# lm4550.net
KiCad netlist of a schematic drawn in Altium Designer
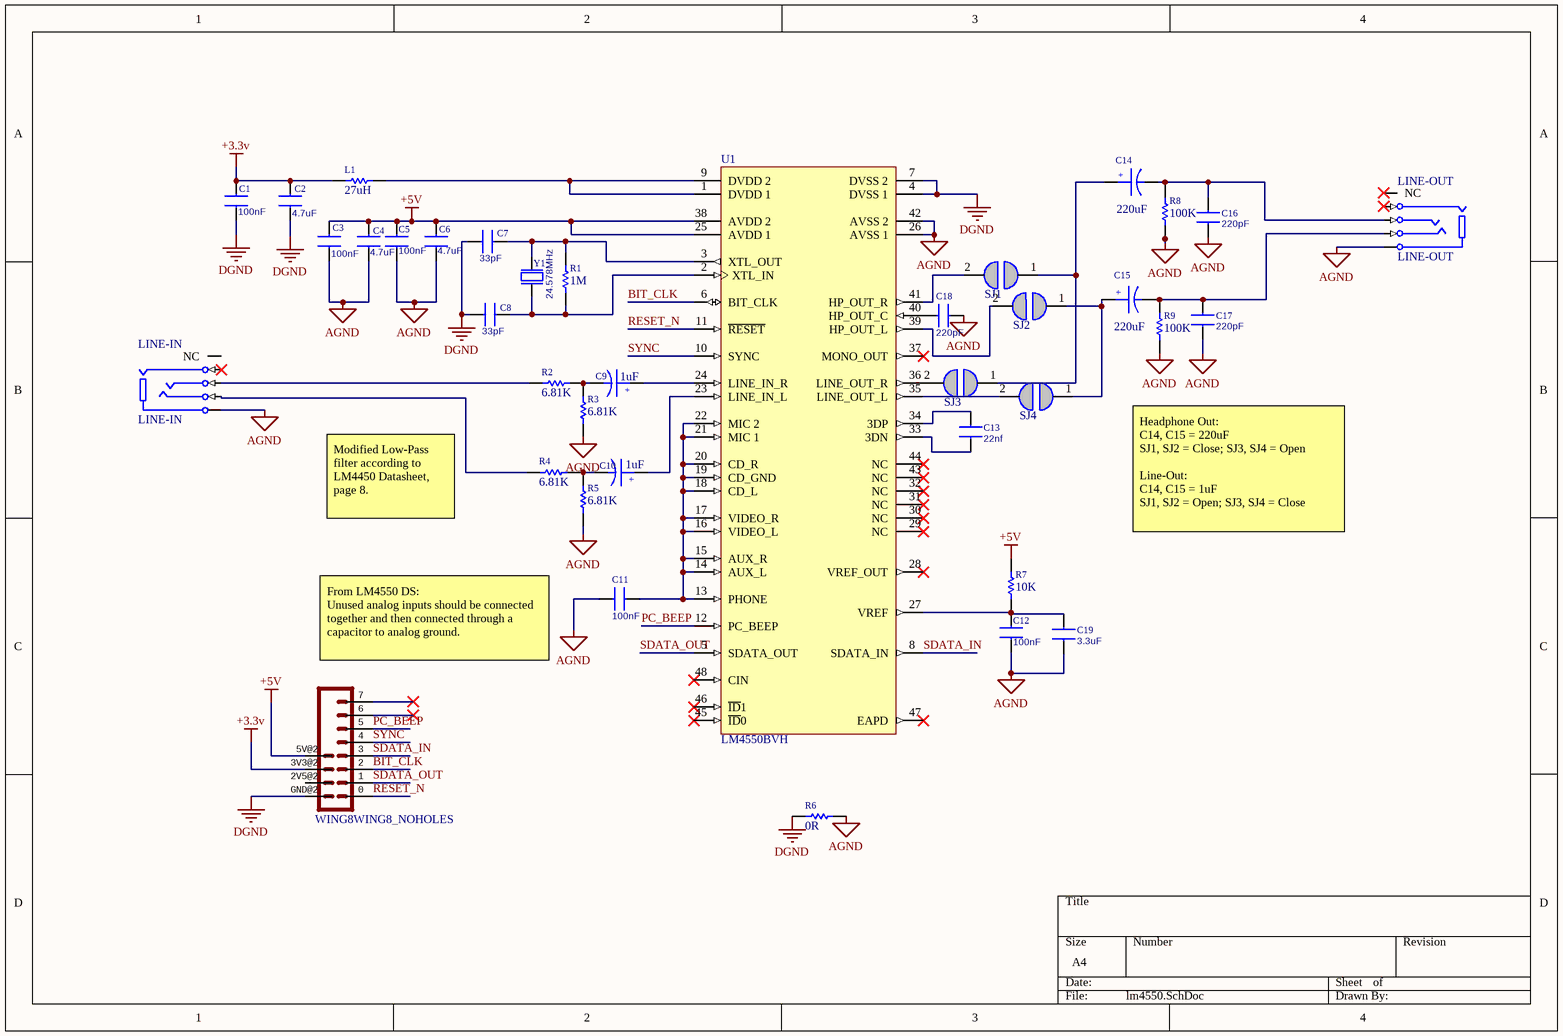
[diagram p0: lm4550.SchDoc]

(export (version "E")
  (design (tool "Eeschema 10.0.6"))
  (components
    (comp (ref "C1")
      (value "100nF")
      (footprint "MH - RCLDSX:C0603")
      (description "Ceramic Capactor size 0603")
      (libsource (lib "MH - RCLDSX") (part "C0603"))
    )
    (comp (ref "C2")
      (value "4.7uF")
      (footprint "C0805")
      (description "Ceramic Capactor size 0805")
      (libsource (lib "MH - RCLDSX") (part "C0805"))
    )
    (comp (ref "C3")
      (value "100nF")
      (footprint "C0603")
      (description "Ceramic Capactor size 0603")
      (libsource (lib "MH - RCLDSX") (part "C0603"))
    )
    (comp (ref "C4")
      (value "4.7uF")
      (footprint "C0805")
      (description "Ceramic Capactor size 0805")
      (libsource (lib "MH - RCLDSX") (part "C0805"))
    )
    (comp (ref "C5")
      (value "100nF")
      (footprint "C0603")
      (description "Ceramic Capactor size 0603")
      (libsource (lib "MH - RCLDSX") (part "C0603"))
    )
    (comp (ref "C6")
      (value "4.7uF")
      (footprint "C0805")
      (description "Ceramic Capactor size 0805")
      (libsource (lib "MH - RCLDSX") (part "C0805"))
    )
    (comp (ref "C7")
      (value "33pF")
      (footprint "C0603")
      (description "Ceramic Capactor size 0603")
      (libsource (lib "MH - RCLDSX") (part "C0603"))
    )
    (comp (ref "C8")
      (value "33pF")
      (footprint "C0603")
      (description "Ceramic Capactor size 0603")
      (libsource (lib "MH - RCLDSX") (part "C0603"))
    )
    (comp (ref "C9")
      (value "1uF")
      (footprint "CPM3216")
      (description "Tantalium Capacitor size A (3216 Metric)")
      (libsource (lib "MH - RCLDSX") (part "CPM3216"))
    )
    (comp (ref "C10")
      (value "1uF")
      (footprint "CPM3216")
      (description "Tantalium Capacitor size A (3216 Metric)")
      (libsource (lib "MH - RCLDSX") (part "CPM3216"))
    )
    (comp (ref "C11")
      (value "100nF")
      (footprint "C0603")
      (description "Ceramic Capactor size 0603")
      (libsource (lib "MH - RCLDSX") (part "C0603"))
    )
    (comp (ref "C12")
      (value "100nF")
      (footprint "C0603")
      (description "Ceramic Capactor size 0603")
      (libsource (lib "MH - RCLDSX") (part "C0603"))
    )
    (comp (ref "C13")
      (value "22nf")
      (footprint "C0603")
      (description "Ceramic Capactor size 0603")
      (libsource (lib "MH - RCLDSX") (part "C0603"))
    )
    (comp (ref "C14")
      (value "220uF")
      (footprint "CPM7343")
      (description "Tantalium Capacitor size D (7343 Metric)")
      (libsource (lib "MH - RCLDSX") (part "CPM7343"))
    )
    (comp (ref "C15")
      (value "220uF")
      (footprint "CPM7343")
      (description "Tantalium Capacitor size D (7343 Metric)")
      (libsource (lib "MH - RCLDSX") (part "CPM7343"))
    )
    (comp (ref "C16")
      (value "220pF")
      (footprint "C0805")
      (description "Ceramic Capactor size 0805")
      (libsource (lib "MH - RCLDSX") (part "C0805"))
    )
    (comp (ref "C17")
      (value "220pF")
      (footprint "C0805")
      (description "Ceramic Capactor size 0805")
      (libsource (lib "MH - RCLDSX") (part "C0805"))
    )
    (comp (ref "C18")
      (value "220pF")
      (footprint "C0805")
      (description "Ceramic Capactor size 0805")
      (libsource (lib "MH - RCLDSX") (part "C0805"))
    )
    (comp (ref "C19")
      (value "3.3uF")
      (footprint "C0805")
      (description "Ceramic Capactor size 0805")
      (libsource (lib "MH - RCLDSX") (part "C0805"))
    )
    (comp (ref "L1")
      (value "27uH")
      (footprint "R0805")
      (description "SMD Chip Inductor size 0805")
      (libsource (lib "MH - RCLDSX") (part "R0805"))
    )
    (comp (ref "LINE-IN")
      (value "LINE-IN")
      (footprint "PJ-386D")
      (description "Phone Jack, PJ-386D Series, Right Angle, SM, 4-Conductor Open Circuit")
      (fields (field (name "PUBLISHER") "Altium Limited"))
      (libsource (lib "Contact Technology Phone Jack") (part "TSH-3864D"))
    )
    (comp (ref "LINE-OUT")
      (value "LINE-OUT")
      (footprint "PJ-386D")
      (description "Phone Jack, PJ-386D Series, Right Angle, SM, 4-Conductor Open Circuit")
      (fields (field (name "PUBLISHER") "Altium Limited"))
      (libsource (lib "Contact Technology Phone Jack") (part "TSH-3864D"))
    )
    (comp (ref "P1")
      (value "WING8WING8_NOHOLES")
      (footprint "WINGSIDE_8BIT_NOHOLES")
      (libsource (lib "Papilio") (part "WING8WING8_NOHOLES"))
    )
    (comp (ref "R1")
      (value "1M")
      (footprint "R0805")
      (description "Chip Resistor size 0805")
      (libsource (lib "MH - RCLDSX") (part "R0805"))
    )
    (comp (ref "R2")
      (value "6.81K")
      (footprint "R0805")
      (description "Chip Resistor size 0805")
      (libsource (lib "MH - RCLDSX") (part "R0805"))
    )
    (comp (ref "R3")
      (value "6.81K")
      (footprint "R0805")
      (description "Chip Resistor size 0805")
      (libsource (lib "MH - RCLDSX") (part "R0805"))
    )
    (comp (ref "R4")
      (value "6.81K")
      (footprint "R0805")
      (description "Chip Resistor size 0805")
      (libsource (lib "MH - RCLDSX") (part "R0805"))
    )
    (comp (ref "R5")
      (value "6.81K")
      (footprint "R0805")
      (description "Chip Resistor size 0805")
      (libsource (lib "MH - RCLDSX") (part "R0805"))
    )
    (comp (ref "R6")
      (value "0R")
      (footprint "R0805")
      (description "Chip Resistor size 0805")
      (libsource (lib "MH - RCLDSX") (part "R0805"))
    )
    (comp (ref "R7")
      (value "10K")
      (footprint "R0805")
      (description "Chip Resistor size 0805")
      (libsource (lib "MH - RCLDSX") (part "R0805"))
    )
    (comp (ref "R8")
      (value "100K")
      (footprint "R0805")
      (description "Chip Resistor size 0805")
      (libsource (lib "MH - RCLDSX") (part "R0805"))
    )
    (comp (ref "R9")
      (value "100K")
      (footprint "R0805")
      (description "Chip Resistor size 0805")
      (libsource (lib "MH - RCLDSX") (part "R0805"))
    )
    (comp (ref "SJ1")
      (value "Solder Junction")
      (footprint "Solde Junction")
      (libsource (lib "MH - Connectors") (part "Solder Junction"))
    )
    (comp (ref "SJ2")
      (value "Solder Junction")
      (footprint "Solde Junction")
      (libsource (lib "MH - Connectors") (part "Solder Junction"))
    )
    (comp (ref "SJ3")
      (value "Solder Junction")
      (footprint "Solde Junction")
      (libsource (lib "MH - Connectors") (part "Solder Junction"))
    )
    (comp (ref "SJ4")
      (value "Solder Junction")
      (footprint "Solde Junction")
      (libsource (lib "MH - Connectors") (part "Solder Junction"))
    )
    (comp (ref "U1")
      (value "LM4550BVH")
      (footprint "VBH48A_N")
      (description "AC '97 Rev 2.1 Codec with Sample Rate Conversion and National 3D Sound, 48-pin LQFP")
      (fields
        (field (name "MANUFACTURER") "National Semiconductor")
        (field (name "PUBLISHER") "Altium Limited")
      )
      (libsource (lib "NSC OtherParts") (part "LM4550BVH"))
    )
    (comp (ref "Y1")
      (value "24.578MHz")
      (footprint "HC-49-S3")
      (description "XTAL Trough Hole")
      (libsource (lib "MH - RCLDSX") (part "XTAL_TH"))
    )
  )
  (nets
    (net (code "1") (name "+3.3v") (class "Default")
      (node (ref "C1") (pin "2") (pintype "passive"))
      (node (ref "C2") (pin "2") (pintype "passive"))
      (node (ref "L1") (pin "2") (pinfunction "2_2") (pintype "passive"))
      (node (ref "P1") (pin "3V3@2") (pinfunction "3V3_3V3@2") (pintype "passive"))
    )
    (net (code "2") (name "+5V") (class "Default")
      (node (ref "C3") (pin "2") (pintype "passive"))
      (node (ref "C4") (pin "2") (pintype "passive"))
      (node (ref "C5") (pin "2") (pintype "passive"))
      (node (ref "C6") (pin "2") (pintype "passive"))
      (node (ref "P1") (pin "5V@2") (pinfunction "5V_5V@2") (pintype "passive"))
      (node (ref "R7") (pin "2") (pinfunction "2_2") (pintype "passive"))
      (node (ref "U1") (pin "25") (pinfunction "AVDD_1_25") (pintype "power_in"))
      (node (ref "U1") (pin "38") (pinfunction "AVDD_2_38") (pintype "power_in"))
    )
    (net (code "3") (name "/BIT_CLK") (class "Default")
      (node (ref "P1") (pin "2") (pinfunction "3_2") (pintype "passive"))
      (node (ref "U1") (pin "6") (pinfunction "BIT_CLK_6") (pintype "bidirectional"))
    )
    (net (code "4") (name "/PC_BEEP") (class "Default")
      (node (ref "P1") (pin "5") (pinfunction "6_5") (pintype "passive"))
      (node (ref "U1") (pin "12") (pinfunction "PC_BEEP_12") (pintype "input"))
    )
    (net (code "5") (name "/RESET_N") (class "Default")
      (node (ref "P1") (pin "0") (pinfunction "1_0") (pintype "passive"))
      (node (ref "U1") (pin "11") (pinfunction "~{RESET}_11") (pintype "input"))
    )
    (net (code "6") (name "/SDATA_IN") (class "Default")
      (node (ref "P1") (pin "3") (pinfunction "4_3") (pintype "passive"))
      (node (ref "U1") (pin "8") (pinfunction "SDATA_IN_8") (pintype "output"))
    )
    (net (code "7") (name "/SDATA_OUT") (class "Default")
      (node (ref "P1") (pin "1") (pinfunction "2_1") (pintype "passive"))
      (node (ref "U1") (pin "5") (pinfunction "SDATA_OUT_5") (pintype "input"))
    )
    (net (code "8") (name "/SYNC") (class "Default")
      (node (ref "P1") (pin "4") (pinfunction "5_4") (pintype "passive"))
      (node (ref "U1") (pin "10") (pinfunction "SYNC_10") (pintype "input"))
    )
    (net (code "9") (name "AGND") (class "Default")
      (node (ref "C11") (pin "2") (pintype "passive"))
      (node (ref "C12") (pin "1") (pintype "passive"))
      (node (ref "C16") (pin "1") (pintype "passive"))
      (node (ref "C17") (pin "1") (pintype "passive"))
      (node (ref "C18") (pin "1") (pintype "passive"))
      (node (ref "C19") (pin "1") (pintype "passive"))
      (node (ref "C3") (pin "1") (pintype "passive"))
      (node (ref "C4") (pin "1") (pintype "passive"))
      (node (ref "C5") (pin "1") (pintype "passive"))
      (node (ref "C6") (pin "1") (pintype "passive"))
      (node (ref "LINE-IN") (pin "1") (pinfunction "S_1") (pintype "power_in"))
      (node (ref "LINE-OUT") (pin "1") (pinfunction "S_1") (pintype "power_in"))
      (node (ref "R3") (pin "1") (pinfunction "1_1") (pintype "passive"))
      (node (ref "R5") (pin "1") (pinfunction "1_1") (pintype "passive"))
      (node (ref "R6") (pin "2") (pinfunction "2_2") (pintype "passive"))
      (node (ref "R8") (pin "1") (pinfunction "1_1") (pintype "passive"))
      (node (ref "R9") (pin "1") (pinfunction "1_1") (pintype "passive"))
      (node (ref "U1") (pin "26") (pinfunction "AVSS_1_26") (pintype "power_in"))
      (node (ref "U1") (pin "42") (pinfunction "AVSS_2_42") (pintype "power_in"))
    )
    (net (code "10") (name "DGND") (class "Default")
      (node (ref "C1") (pin "1") (pintype "passive"))
      (node (ref "C2") (pin "1") (pintype "passive"))
      (node (ref "C7") (pin "2") (pintype "passive"))
      (node (ref "C8") (pin "2") (pintype "passive"))
      (node (ref "P1") (pin "GND@2") (pinfunction "GND_GND@2") (pintype "passive"))
      (node (ref "R6") (pin "1") (pinfunction "1_1") (pintype "passive"))
      (node (ref "U1") (pin "4") (pinfunction "DVSS_1_4") (pintype "power_in"))
      (node (ref "U1") (pin "7") (pinfunction "DVSS_2_7") (pintype "power_in"))
    )
    (net (code "11") (name "Net-(C9-Pad2)") (class "Default")
      (node (ref "C9") (pin "2") (pinfunction "2_2") (pintype "passive"))
      (node (ref "R2") (pin "2") (pinfunction "2_2") (pintype "passive"))
      (node (ref "R3") (pin "2") (pinfunction "2_2") (pintype "passive"))
    )
    (net (code "12") (name "Net-(C10-Pad2)") (class "Default")
      (node (ref "C10") (pin "2") (pinfunction "2_2") (pintype "passive"))
      (node (ref "R4") (pin "2") (pinfunction "2_2") (pintype "passive"))
      (node (ref "R5") (pin "2") (pinfunction "2_2") (pintype "passive"))
    )
    (net (code "13") (name "Net-(C14-Pad1)") (class "Default")
      (node (ref "C14") (pin "1") (pinfunction "1_1") (pintype "passive"))
      (node (ref "SJ1") (pin "1") (pinfunction "1_1") (pintype "passive"))
      (node (ref "SJ3") (pin "1") (pinfunction "1_1") (pintype "passive"))
    )
    (net (code "14") (name "Net-(C15-Pad1)") (class "Default")
      (node (ref "C15") (pin "1") (pinfunction "1_1") (pintype "passive"))
      (node (ref "SJ2") (pin "1") (pinfunction "1_1") (pintype "passive"))
      (node (ref "SJ4") (pin "1") (pinfunction "1_1") (pintype "passive"))
    )
    (net (code "15") (name "Net-(LINE-IN-R)") (class "Default")
      (node (ref "LINE-IN") (pin "3") (pinfunction "R_3") (pintype "input"))
      (node (ref "R4") (pin "1") (pinfunction "1_1") (pintype "passive"))
    )
    (net (code "16") (name "Net-(LINE-IN-T)") (class "Default")
      (node (ref "LINE-IN") (pin "2") (pinfunction "T_2") (pintype "input"))
      (node (ref "R2") (pin "1") (pinfunction "1_1") (pintype "passive"))
    )
    (net (code "17") (name "Net-(LINE-OUT-R)") (class "Default")
      (node (ref "C15") (pin "2") (pinfunction "2_2") (pintype "passive"))
      (node (ref "C17") (pin "2") (pintype "passive"))
      (node (ref "LINE-OUT") (pin "3") (pinfunction "R_3") (pintype "input"))
      (node (ref "R9") (pin "2") (pinfunction "2_2") (pintype "passive"))
    )
    (net (code "18") (name "Net-(LINE-OUT-T)") (class "Default")
      (node (ref "C14") (pin "2") (pinfunction "2_2") (pintype "passive"))
      (node (ref "C16") (pin "2") (pintype "passive"))
      (node (ref "LINE-OUT") (pin "2") (pinfunction "T_2") (pintype "input"))
      (node (ref "R8") (pin "2") (pinfunction "2_2") (pintype "passive"))
    )
    (net (code "19") (name "Net-(U1-3DN)") (class "Default")
      (node (ref "C13") (pin "2") (pintype "passive"))
      (node (ref "U1") (pin "33") (pinfunction "3DN_33") (pintype "output"))
    )
    (net (code "20") (name "Net-(U1-3DP)") (class "Default")
      (node (ref "C13") (pin "1") (pintype "passive"))
      (node (ref "U1") (pin "34") (pinfunction "3DP_34") (pintype "output"))
    )
    (net (code "21") (name "Net-(U1-AUX_L)") (class "Default")
      (node (ref "C11") (pin "1") (pintype "passive"))
      (node (ref "U1") (pin "13") (pinfunction "PHONE_13") (pintype "input"))
      (node (ref "U1") (pin "14") (pinfunction "AUX_L_14") (pintype "input"))
      (node (ref "U1") (pin "15") (pinfunction "AUX_R_15") (pintype "input"))
      (node (ref "U1") (pin "16") (pinfunction "VIDEO_L_16") (pintype "input"))
      (node (ref "U1") (pin "17") (pinfunction "VIDEO_R_17") (pintype "input"))
      (node (ref "U1") (pin "18") (pinfunction "CD_L_18") (pintype "input"))
      (node (ref "U1") (pin "19") (pinfunction "CD_GND_19") (pintype "input"))
      (node (ref "U1") (pin "20") (pinfunction "CD_R_20") (pintype "input"))
      (node (ref "U1") (pin "21") (pinfunction "MIC_1_21") (pintype "input"))
      (node (ref "U1") (pin "22") (pinfunction "MIC_2_22") (pintype "input"))
    )
    (net (code "22") (name "Net-(U1-DVDD_1)") (class "Default")
      (node (ref "L1") (pin "1") (pinfunction "1_1") (pintype "passive"))
      (node (ref "U1") (pin "1") (pinfunction "DVDD_1_1") (pintype "power_in"))
      (node (ref "U1") (pin "9") (pinfunction "DVDD_2_9") (pintype "power_in"))
    )
    (net (code "23") (name "Net-(U1-HP_OUT_C)") (class "Default")
      (node (ref "C18") (pin "2") (pintype "passive"))
      (node (ref "U1") (pin "40") (pinfunction "HP_OUT_C_40") (pintype "input"))
    )
    (net (code "24") (name "Net-(U1-HP_OUT_L)") (class "Default")
      (node (ref "SJ2") (pin "2") (pinfunction "2_2") (pintype "passive"))
      (node (ref "U1") (pin "39") (pinfunction "HP_OUT_L_39") (pintype "output"))
    )
    (net (code "25") (name "Net-(U1-HP_OUT_R)") (class "Default")
      (node (ref "SJ1") (pin "2") (pinfunction "2_2") (pintype "passive"))
      (node (ref "U1") (pin "41") (pinfunction "HP_OUT_R_41") (pintype "output"))
    )
    (net (code "26") (name "Net-(U1-LINE_IN_L)") (class "Default")
      (node (ref "C10") (pin "1") (pinfunction "1_1") (pintype "passive"))
      (node (ref "U1") (pin "23") (pinfunction "LINE_IN_L_23") (pintype "input"))
    )
    (net (code "27") (name "Net-(U1-LINE_IN_R)") (class "Default")
      (node (ref "C9") (pin "1") (pinfunction "1_1") (pintype "passive"))
      (node (ref "U1") (pin "24") (pinfunction "LINE_IN_R_24") (pintype "input"))
    )
    (net (code "28") (name "Net-(U1-LINE_OUT_L)") (class "Default")
      (node (ref "SJ4") (pin "2") (pinfunction "2_2") (pintype "passive"))
      (node (ref "U1") (pin "35") (pinfunction "LINE_OUT_L_35") (pintype "output"))
    )
    (net (code "29") (name "Net-(U1-LINE_OUT_R)") (class "Default")
      (node (ref "SJ3") (pin "2") (pinfunction "2_2") (pintype "passive"))
      (node (ref "U1") (pin "36") (pinfunction "LINE_OUT_R_36") (pintype "output"))
    )
    (net (code "30") (name "Net-(U1-VREF)") (class "Default")
      (node (ref "C12") (pin "2") (pintype "passive"))
      (node (ref "C19") (pin "2") (pintype "passive"))
      (node (ref "R7") (pin "1") (pinfunction "1_1") (pintype "passive"))
      (node (ref "U1") (pin "27") (pinfunction "VREF_27") (pintype "output"))
    )
    (net (code "31") (name "Net-(U1-XTL_IN)") (class "Default")
      (node (ref "C8") (pin "1") (pintype "passive"))
      (node (ref "R1") (pin "1") (pinfunction "1_1") (pintype "passive"))
      (node (ref "U1") (pin "2") (pinfunction "XTL_IN_2") (pintype "input"))
      (node (ref "Y1") (pin "2") (pintype "passive"))
    )
    (net (code "32") (name "Net-(U1-XTL_OUT)") (class "Default")
      (node (ref "C7") (pin "1") (pintype "passive"))
      (node (ref "R1") (pin "2") (pinfunction "2_2") (pintype "passive"))
      (node (ref "U1") (pin "3") (pinfunction "XTL_OUT_3") (pintype "output"))
      (node (ref "Y1") (pin "1") (pintype "passive"))
    )
    (net (code "33") (name "unconnected-(LINE-IN-NC-Pad10)") (class "Default")
      (node (ref "LINE-IN") (pin "10") (pinfunction "NC_10") (pintype "passive"))
    )
    (net (code "34") (name "unconnected-(LINE-IN-SN-Pad4)") (class "Default")
      (node (ref "LINE-IN") (pin "4") (pinfunction "SN_4") (pintype "input+no_connect"))
    )
    (net (code "35") (name "unconnected-(LINE-OUT-NC-Pad10)") (class "Default")
      (node (ref "LINE-OUT") (pin "10") (pinfunction "NC_10") (pintype "passive+no_connect"))
    )
    (net (code "36") (name "unconnected-(LINE-OUT-SN-Pad4)") (class "Default")
      (node (ref "LINE-OUT") (pin "4") (pinfunction "SN_4") (pintype "input+no_connect"))
    )
    (net (code "37") (name "unconnected-(P1-2V5-Pad2V5@2)") (class "Default")
      (node (ref "P1") (pin "2V5@2") (pinfunction "2V5_2V5@2") (pintype "passive"))
    )
    (net (code "38") (name "unconnected-(P1-7-Pad6)") (class "Default")
      (node (ref "P1") (pin "6") (pinfunction "7_6") (pintype "passive+no_connect"))
    )
    (net (code "39") (name "unconnected-(P1-8-Pad7)") (class "Default")
      (node (ref "P1") (pin "7") (pinfunction "8_7") (pintype "passive+no_connect"))
    )
    (net (code "40") (name "unconnected-(U1-CIN-Pad48)") (class "Default")
      (node (ref "U1") (pin "48") (pinfunction "CIN_48") (pintype "input+no_connect"))
    )
    (net (code "41") (name "unconnected-(U1-EAPD-Pad47)") (class "Default")
      (node (ref "U1") (pin "47") (pinfunction "EAPD_47") (pintype "output+no_connect"))
    )
    (net (code "42") (name "unconnected-(U1-MONO_OUT-Pad37)") (class "Default")
      (node (ref "U1") (pin "37") (pinfunction "MONO_OUT_37") (pintype "output+no_connect"))
    )
    (net (code "43") (name "unconnected-(U1-NC-Pad29)") (class "Default")
      (node (ref "U1") (pin "29") (pinfunction "NC_29") (pintype "passive+no_connect"))
    )
    (net (code "44") (name "unconnected-(U1-NC-Pad30)") (class "Default")
      (node (ref "U1") (pin "30") (pinfunction "NC_30") (pintype "passive+no_connect"))
    )
    (net (code "45") (name "unconnected-(U1-NC-Pad31)") (class "Default")
      (node (ref "U1") (pin "31") (pinfunction "NC_31") (pintype "passive+no_connect"))
    )
    (net (code "46") (name "unconnected-(U1-NC-Pad32)") (class "Default")
      (node (ref "U1") (pin "32") (pinfunction "NC_32") (pintype "passive+no_connect"))
    )
    (net (code "47") (name "unconnected-(U1-NC-Pad43)") (class "Default")
      (node (ref "U1") (pin "43") (pinfunction "NC_43") (pintype "passive+no_connect"))
    )
    (net (code "48") (name "unconnected-(U1-NC-Pad44)") (class "Default")
      (node (ref "U1") (pin "44") (pinfunction "NC_44") (pintype "passive+no_connect"))
    )
    (net (code "49") (name "unconnected-(U1-VREF_OUT-Pad28)") (class "Default")
      (node (ref "U1") (pin "28") (pinfunction "VREF_OUT_28") (pintype "output+no_connect"))
    )
    (net (code "50") (name "unconnected-(U1-~{ID}0-Pad45)") (class "Default")
      (node (ref "U1") (pin "45") (pinfunction "~{ID}0_45") (pintype "input+no_connect"))
    )
    (net (code "51") (name "unconnected-(U1-~{ID}1-Pad46)") (class "Default")
      (node (ref "U1") (pin "46") (pinfunction "~{ID}1_46") (pintype "input+no_connect"))
    )
  )
)
